# MCU.net
KiCad netlist of a schematic drawn in Altium Designer
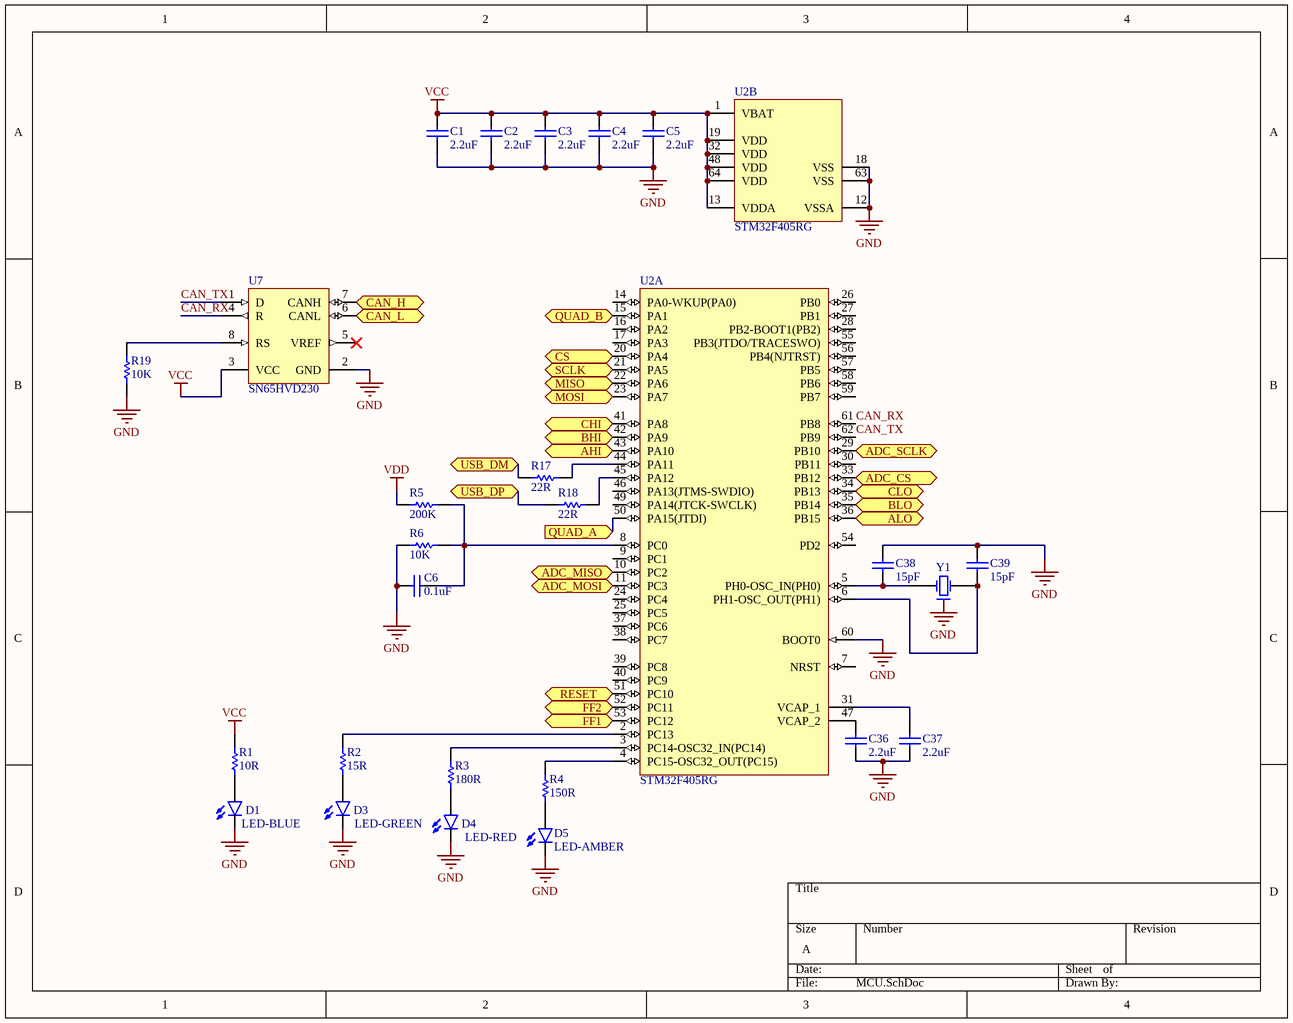
[diagram p0: MCU.SchDoc]

(export (version "E")
  (design (tool "Eeschema 10.0.6"))
  (components
    (comp (ref "C1")
      (value "2.2uF")
      (footprint "CAPC0603(1608)55_N")
      (description "CAP 2.2uF 16V Â±10% 0603 (1608 Metric) Thickness 0.55mm SMD")
      (fields (field (name "TOLERANCE") "Â±10%"))
      (libsource (lib "Altium Content Vault") (part "CMP-1035-02762-1"))
    )
    (comp (ref "C2")
      (value "2.2uF")
      (footprint "CAPC0603(1608)55_N")
      (description "CAP 2.2uF 16V Â±10% 0603 (1608 Metric) Thickness 0.55mm SMD")
      (fields (field (name "TOLERANCE") "Â±10%"))
      (libsource (lib "Altium Content Vault") (part "CMP-1035-02762-1"))
    )
    (comp (ref "C3")
      (value "2.2uF")
      (footprint "CAPC0603(1608)55_N")
      (description "CAP 2.2uF 16V Â±10% 0603 (1608 Metric) Thickness 0.55mm SMD")
      (fields (field (name "TOLERANCE") "Â±10%"))
      (libsource (lib "Altium Content Vault") (part "CMP-1035-02762-1"))
    )
    (comp (ref "C4")
      (value "2.2uF")
      (footprint "CAPC0603(1608)55_N")
      (description "CAP 2.2uF 16V Â±10% 0603 (1608 Metric) Thickness 0.55mm SMD")
      (fields (field (name "TOLERANCE") "Â±10%"))
      (libsource (lib "Altium Content Vault") (part "CMP-1035-02762-1"))
    )
    (comp (ref "C5")
      (value "2.2uF")
      (footprint "CAPC0603(1608)55_N")
      (description "CAP 2.2uF 16V Â±10% 0603 (1608 Metric) Thickness 0.55mm SMD")
      (fields (field (name "TOLERANCE") "Â±10%"))
      (libsource (lib "Altium Content Vault") (part "CMP-1035-02762-1"))
    )
    (comp (ref "C6")
      (value "0.1uF")
      (footprint "CAPC0603(1608)100_L")
      (description "CAP 100nF 50V Â±5% 0603 (1608 Metric) Thickness 1mm SMD")
      (fields (field (name "TOLERANCE") "Â±5%"))
      (libsource (lib "Altium Content Vault") (part "CMP-1035-02591-1"))
    )
    (comp (ref "C36")
      (value "2.2uF")
      (footprint "CAPC0603(1608)55_N")
      (description "CAP 2.2uF 16V Â±10% 0603 (1608 Metric) Thickness 0.55mm SMD")
      (fields (field (name "TOLERANCE") "Â±10%"))
      (libsource (lib "Altium Content Vault") (part "CMP-1035-02762-1"))
    )
    (comp (ref "C37")
      (value "2.2uF")
      (footprint "CAPC0603(1608)55_N")
      (description "CAP 2.2uF 16V Â±10% 0603 (1608 Metric) Thickness 0.55mm SMD")
      (fields (field (name "TOLERANCE") "Â±10%"))
      (libsource (lib "Altium Content Vault") (part "CMP-1035-02762-1"))
    )
    (comp (ref "C38")
      (value "15pF")
      (footprint "CAPC0603(1608)100_L")
      (description "CAP 15pF 100V Â±0.25pF 0603 (1608 Metric) Thickness 1mm SMD")
      (fields (field (name "TOLERANCE") "Â±0.25pF"))
      (libsource (lib "Altium Content Vault") (part "CAP"))
    )
    (comp (ref "C39")
      (value "15pF")
      (footprint "CAPC0603(1608)100_L")
      (description "CAP 15pF 100V Â±0.25pF 0603 (1608 Metric) Thickness 1mm SMD")
      (fields (field (name "TOLERANCE") "Â±0.25pF"))
      (libsource (lib "Altium Content Vault") (part "CAP"))
    )
    (comp (ref "D1")
      (value "LED-BLUE")
      (footprint "LED-1206")
      (libsource (lib "Components") (part "LED-BLUE1206"))
    )
    (comp (ref "D3")
      (value "LED-GREEN")
      (footprint "LED-1206")
      (libsource (lib "Components") (part "LED-GREEN1206"))
    )
    (comp (ref "D4")
      (value "LED-RED")
      (footprint "LED-1206")
      (libsource (lib "Components") (part "LED-RED1206"))
    )
    (comp (ref "D5")
      (value "LED-AMBER")
      (footprint "LED-1206")
      (libsource (lib "Components") (part "LED-AMBER1206"))
    )
    (comp (ref "R1")
      (value "10R")
      (footprint "RESC0603(1608)_N")
      (description "10R 0.1W 5% 0603 (1608 Metric)  SMD")
      (fields (field (name "TOLERANCE") "5 %") (field (name "POWER") "0.1 W"))
      (libsource (lib "Altium Content Vault") (part "CMP-1012-00026-1"))
    )
    (comp (ref "R2")
      (value "15R")
      (footprint "RESC0603(1608)_N")
      (description "15R 0.1W 5% 0603 (1608 Metric)  SMD")
      (fields (field (name "TOLERANCE") "5 %") (field (name "POWER") "0.1 W"))
      (libsource (lib "Altium Content Vault") (part "CMP-1012-00030-1"))
    )
    (comp (ref "R3")
      (value "180R")
      (footprint "RESC0603(1608)_N")
      (description "180R 0.1W 5% 0603 (1608 Metric)  SMD")
      (fields (field (name "POWER") "0.1 W") (field (name "TOLERANCE") "5 %"))
      (libsource (lib "Altium Content Vault") (part "CMP-1012-00056-1"))
    )
    (comp (ref "R4")
      (value "150R")
      (footprint "RESC0603(1608)_N")
      (description "150R 0.1W 5% 0603 (1608 Metric)  SMD")
      (fields (field (name "POWER") "0.1 W") (field (name "TOLERANCE") "5 %"))
      (libsource (lib "Altium Content Vault") (part "CMP-1012-00054-1"))
    )
    (comp (ref "R5")
      (value "200K")
      (footprint "RESC0603(1608)_N")
      (description "200K 0.1W 5% 0603 (1608 Metric)  SMD")
      (fields (field (name "POWER") "0.1 W") (field (name "TOLERANCE") "5 %"))
      (libsource (lib "Altium Content Vault") (part "CMP-1012-00129-1"))
    )
    (comp (ref "R6")
      (value "10K")
      (footprint "RESC0603(1608)_N")
      (description "10K 0.1W 5% 0603 (1608 Metric)  SMD")
      (fields (field (name "TOLERANCE") "5 %") (field (name "POWER") "0.1 W"))
      (libsource (lib "Altium Content Vault") (part "RES"))
    )
    (comp (ref "R17")
      (value "22R")
      (footprint "RESC0603(1608)_M")
      (description "22R 0.1W 5% 0603 (1608 Metric)  SMD")
      (fields (field (name "POWER") "0.1 W") (field (name "TOLERANCE") "5 %"))
      (libsource (lib "Altium Content Vault") (part "RES"))
    )
    (comp (ref "R18")
      (value "22R")
      (footprint "RESC0603(1608)_M")
      (description "22R 0.1W 5% 0603 (1608 Metric)  SMD")
      (fields (field (name "POWER") "0.1 W") (field (name "TOLERANCE") "5 %"))
      (libsource (lib "Altium Content Vault") (part "RES"))
    )
    (comp (ref "R19")
      (value "10K")
      (footprint "RESC0603(1608)_M")
      (description "10K 0.1W 5% 0603 (1608 Metric)  SMD")
      (fields (field (name "TOLERANCE") "5 %") (field (name "POWER") "0.1 W"))
      (libsource (lib "Altium Content Vault") (part "RES"))
    )
    (comp (ref "U2") (value "STM32F405RG") (libsource (lib "Components") (part "MC-ARM-STM32F4X5-SQ64")))
    (comp (ref "U7")
      (value "SN65HVD230")
      (footprint "D8_N")
      (fields (field (name "MANUFACTURER") "Texas Instruments") (field (name "PARTNUMBER") "SN65HVD230DR"))
      (libsource (lib "Altium Content Vault") (part "CMP-0315-00015-1"))
    )
    (comp (ref "Y1")
      (value "~")
      (footprint "ABRA-ABM3B-4_V")
      (libsource (lib "Components") (part "ABRA-ABM3B-4"))
    )
  )
  (nets
    (net (code "1") (name "/ADC_CS") (class "Default")
      (node (ref "U2") (pin "33") (pinfunction "PB12_33") (pintype "bidirectional"))
    )
    (net (code "2") (name "/ADC_MISO") (class "Default")
      (node (ref "U2") (pin "10") (pinfunction "PC2_10") (pintype "bidirectional"))
    )
    (net (code "3") (name "/ADC_MOSI") (class "Default")
      (node (ref "U2") (pin "11") (pinfunction "PC3_11") (pintype "bidirectional"))
    )
    (net (code "4") (name "/ADC_SCLK") (class "Default")
      (node (ref "U2") (pin "29") (pinfunction "PB10_29") (pintype "bidirectional"))
    )
    (net (code "5") (name "/AHI") (class "Default")
      (node (ref "U2") (pin "43") (pinfunction "PA10_43") (pintype "bidirectional"))
    )
    (net (code "6") (name "/ALO") (class "Default")
      (node (ref "U2") (pin "36") (pinfunction "PB15_36") (pintype "bidirectional"))
    )
    (net (code "7") (name "/BHI") (class "Default")
      (node (ref "U2") (pin "42") (pinfunction "PA9_42") (pintype "bidirectional"))
    )
    (net (code "8") (name "/BLO") (class "Default")
      (node (ref "U2") (pin "35") (pinfunction "PB14_35") (pintype "bidirectional"))
    )
    (net (code "9") (name "/CAN_H") (class "Default")
      (node (ref "U7") (pin "7") (pinfunction "CANH_7") (pintype "bidirectional"))
    )
    (net (code "10") (name "/CAN_L") (class "Default")
      (node (ref "U7") (pin "6") (pinfunction "CANL_6") (pintype "bidirectional"))
    )
    (net (code "11") (name "/CAN_RX") (class "Default")
      (node (ref "U2") (pin "61") (pinfunction "PB8_61") (pintype "bidirectional"))
      (node (ref "U7") (pin "4") (pinfunction "R_4") (pintype "output"))
    )
    (net (code "12") (name "/CAN_TX") (class "Default")
      (node (ref "U2") (pin "62") (pinfunction "PB9_62") (pintype "bidirectional"))
      (node (ref "U7") (pin "1") (pinfunction "D_1") (pintype "input"))
    )
    (net (code "13") (name "/CHI") (class "Default")
      (node (ref "U2") (pin "41") (pinfunction "PA8_41") (pintype "bidirectional"))
    )
    (net (code "14") (name "/CLO") (class "Default")
      (node (ref "U2") (pin "34") (pinfunction "PB13_34") (pintype "bidirectional"))
    )
    (net (code "15") (name "/CS") (class "Default")
      (node (ref "U2") (pin "20") (pinfunction "PA4_20") (pintype "bidirectional"))
    )
    (net (code "16") (name "/FF1") (class "Default")
      (node (ref "U2") (pin "53") (pinfunction "PC12_53") (pintype "bidirectional"))
    )
    (net (code "17") (name "/FF2") (class "Default")
      (node (ref "U2") (pin "52") (pinfunction "PC11_52") (pintype "bidirectional"))
    )
    (net (code "18") (name "/MISO") (class "Default")
      (node (ref "U2") (pin "22") (pinfunction "PA6_22") (pintype "bidirectional"))
    )
    (net (code "19") (name "/MOSI") (class "Default")
      (node (ref "U2") (pin "23") (pinfunction "PA7_23") (pintype "bidirectional"))
    )
    (net (code "20") (name "/QUAD_A") (class "Default")
      (node (ref "U2") (pin "50") (pinfunction "PA15(JTDI)_50") (pintype "bidirectional"))
    )
    (net (code "21") (name "/QUAD_B") (class "Default")
      (node (ref "U2") (pin "15") (pinfunction "PA1_15") (pintype "bidirectional"))
    )
    (net (code "22") (name "/RESET") (class "Default")
      (node (ref "U2") (pin "51") (pinfunction "PC10_51") (pintype "bidirectional"))
    )
    (net (code "23") (name "/SCLK") (class "Default")
      (node (ref "U2") (pin "21") (pinfunction "PA5_21") (pintype "bidirectional"))
    )
    (net (code "24") (name "/USB_DM") (class "Default")
      (node (ref "R17") (pin "1") (pinfunction "1_1") (pintype "passive"))
    )
    (net (code "25") (name "/USB_DP") (class "Default")
      (node (ref "R18") (pin "1") (pinfunction "1_1") (pintype "passive"))
    )
    (net (code "26") (name "GND") (class "Default")
      (node (ref "C1") (pin "1") (pinfunction "1_1") (pintype "passive"))
      (node (ref "C2") (pin "1") (pinfunction "1_1") (pintype "passive"))
      (node (ref "C3") (pin "1") (pinfunction "1_1") (pintype "passive"))
      (node (ref "C36") (pin "1") (pinfunction "1_1") (pintype "passive"))
      (node (ref "C37") (pin "1") (pinfunction "1_1") (pintype "passive"))
      (node (ref "C38") (pin "2") (pinfunction "2_2") (pintype "passive"))
      (node (ref "C39") (pin "2") (pinfunction "2_2") (pintype "passive"))
      (node (ref "C4") (pin "1") (pinfunction "1_1") (pintype "passive"))
      (node (ref "C5") (pin "1") (pinfunction "1_1") (pintype "passive"))
      (node (ref "C6") (pin "1") (pinfunction "1_1") (pintype "passive"))
      (node (ref "D1") (pin "C") (pinfunction "C_C") (pintype "passive"))
      (node (ref "D3") (pin "C") (pinfunction "C_C") (pintype "passive"))
      (node (ref "D4") (pin "C") (pinfunction "C_C") (pintype "passive"))
      (node (ref "D5") (pin "C") (pinfunction "C_C") (pintype "passive"))
      (node (ref "R19") (pin "1") (pinfunction "1_1") (pintype "passive"))
      (node (ref "R6") (pin "1") (pinfunction "1_1") (pintype "passive"))
      (node (ref "U2") (pin "12") (pinfunction "VSSA_12") (pintype "power_in"))
      (node (ref "U2") (pin "18") (pinfunction "VSS_18") (pintype "power_in"))
      (node (ref "U2") (pin "60") (pinfunction "BOOT0_60") (pintype "input"))
      (node (ref "U2") (pin "63") (pinfunction "VSS_63") (pintype "power_in"))
      (node (ref "U7") (pin "2") (pinfunction "GND_2") (pintype "power_in"))
      (node (ref "Y1") (pin "2") (pinfunction "2_2") (pintype "passive"))
    )
    (net (code "27") (name "Net-(D1-PadA)") (class "Default")
      (node (ref "D1") (pin "A") (pinfunction "A_A") (pintype "passive"))
      (node (ref "R1") (pin "1") (pinfunction "1_1") (pintype "passive"))
    )
    (net (code "28") (name "Net-(D3-PadA)") (class "Default")
      (node (ref "D3") (pin "A") (pinfunction "A_A") (pintype "passive"))
      (node (ref "R2") (pin "1") (pinfunction "1_1") (pintype "passive"))
    )
    (net (code "29") (name "Net-(D4-PadA)") (class "Default")
      (node (ref "D4") (pin "A") (pinfunction "A_A") (pintype "passive"))
      (node (ref "R3") (pin "1") (pinfunction "1_1") (pintype "passive"))
    )
    (net (code "30") (name "Net-(D5-PadA)") (class "Default")
      (node (ref "D5") (pin "A") (pinfunction "A_A") (pintype "passive"))
      (node (ref "R4") (pin "1") (pinfunction "1_1") (pintype "passive"))
    )
    (net (code "31") (name "Net-(U2A-PA11)") (class "Default")
      (node (ref "R17") (pin "2") (pinfunction "2_2") (pintype "passive"))
      (node (ref "U2") (pin "44") (pinfunction "PA11_44") (pintype "bidirectional"))
    )
    (net (code "32") (name "Net-(U2A-PA12)") (class "Default")
      (node (ref "R18") (pin "2") (pinfunction "2_2") (pintype "passive"))
      (node (ref "U2") (pin "45") (pinfunction "PA12_45") (pintype "bidirectional"))
    )
    (net (code "33") (name "Net-(U2A-PC0)") (class "Default")
      (node (ref "C6") (pin "2") (pinfunction "2_2") (pintype "passive"))
      (node (ref "R5") (pin "2") (pinfunction "2_2") (pintype "passive"))
      (node (ref "R6") (pin "2") (pinfunction "2_2") (pintype "passive"))
      (node (ref "U2") (pin "8") (pinfunction "PC0_8") (pintype "bidirectional"))
    )
    (net (code "34") (name "Net-(U2A-PC13)") (class "Default")
      (node (ref "R2") (pin "2") (pinfunction "2_2") (pintype "passive"))
      (node (ref "U2") (pin "2") (pinfunction "PC13_2") (pintype "bidirectional"))
    )
    (net (code "35") (name "Net-(U2A-PC14-OSC32_IN(PC14))") (class "Default")
      (node (ref "R3") (pin "2") (pinfunction "2_2") (pintype "passive"))
      (node (ref "U2") (pin "3") (pinfunction "PC14-OSC32_IN(PC14)_3") (pintype "bidirectional"))
    )
    (net (code "36") (name "Net-(U2A-PC15-OSC32_OUT(PC15))") (class "Default")
      (node (ref "R4") (pin "2") (pinfunction "2_2") (pintype "passive"))
      (node (ref "U2") (pin "4") (pinfunction "PC15-OSC32_OUT(PC15)_4") (pintype "bidirectional"))
    )
    (net (code "37") (name "Net-(U2A-PH0-OSC_IN(PH0))") (class "Default")
      (node (ref "C38") (pin "1") (pinfunction "1_1") (pintype "passive"))
      (node (ref "U2") (pin "5") (pinfunction "PH0-OSC_IN(PH0)_5") (pintype "bidirectional"))
      (node (ref "Y1") (pin "1") (pinfunction "X1_1") (pintype "passive"))
    )
    (net (code "38") (name "Net-(U2A-PH1-OSC_OUT(PH1))") (class "Default")
      (node (ref "C39") (pin "1") (pinfunction "1_1") (pintype "passive"))
      (node (ref "U2") (pin "6") (pinfunction "PH1-OSC_OUT(PH1)_6") (pintype "bidirectional"))
      (node (ref "Y1") (pin "3") (pinfunction "X2_3") (pintype "passive"))
    )
    (net (code "39") (name "Net-(U2A-VCAP_1)") (class "Default")
      (node (ref "C37") (pin "2") (pinfunction "2_2") (pintype "passive"))
      (node (ref "U2") (pin "31") (pinfunction "VCAP_1_31") (pintype "power_in"))
    )
    (net (code "40") (name "Net-(U2A-VCAP_2)") (class "Default")
      (node (ref "C36") (pin "2") (pinfunction "2_2") (pintype "passive"))
      (node (ref "U2") (pin "47") (pinfunction "VCAP_2_47") (pintype "power_in"))
    )
    (net (code "41") (name "Net-(U7-RS)") (class "Default")
      (node (ref "R19") (pin "2") (pinfunction "2_2") (pintype "passive"))
      (node (ref "U7") (pin "8") (pinfunction "RS_8") (pintype "input"))
    )
    (net (code "42") (name "VCC") (class "Default")
      (node (ref "C1") (pin "2") (pinfunction "2_2") (pintype "passive"))
      (node (ref "C2") (pin "2") (pinfunction "2_2") (pintype "passive"))
      (node (ref "C3") (pin "2") (pinfunction "2_2") (pintype "passive"))
      (node (ref "C4") (pin "2") (pinfunction "2_2") (pintype "passive"))
      (node (ref "C5") (pin "2") (pinfunction "2_2") (pintype "passive"))
      (node (ref "R1") (pin "2") (pinfunction "2_2") (pintype "passive"))
      (node (ref "U2") (pin "1") (pinfunction "VBAT_1") (pintype "power_in"))
      (node (ref "U2") (pin "13") (pinfunction "VDDA_13") (pintype "power_in"))
      (node (ref "U2") (pin "19") (pinfunction "VDD_19") (pintype "power_in"))
      (node (ref "U2") (pin "32") (pinfunction "VDD_32") (pintype "power_in"))
      (node (ref "U2") (pin "48") (pinfunction "VDD_48") (pintype "power_in"))
      (node (ref "U2") (pin "64") (pinfunction "VDD_64") (pintype "power_in"))
      (node (ref "U7") (pin "3") (pinfunction "VCC_3") (pintype "power_in"))
    )
    (net (code "43") (name "VDD") (class "Default")
      (node (ref "R5") (pin "1") (pinfunction "1_1") (pintype "passive"))
    )
    (net (code "44") (name "unconnected-(U2A-NRST-Pad7)") (class "Default")
      (node (ref "U2") (pin "7") (pinfunction "NRST_7") (pintype "bidirectional"))
    )
    (net (code "45") (name "unconnected-(U2A-PA0-WKUP(PA0)-Pad14)") (class "Default")
      (node (ref "U2") (pin "14") (pinfunction "PA0-WKUP(PA0)_14") (pintype "bidirectional"))
    )
    (net (code "46") (name "unconnected-(U2A-PA2-Pad16)") (class "Default")
      (node (ref "U2") (pin "16") (pinfunction "PA2_16") (pintype "bidirectional"))
    )
    (net (code "47") (name "unconnected-(U2A-PA3-Pad17)") (class "Default")
      (node (ref "U2") (pin "17") (pinfunction "PA3_17") (pintype "bidirectional"))
    )
    (net (code "48") (name "unconnected-(U2A-PA13(JTMS-SWDIO)-Pad46)") (class "Default")
      (node (ref "U2") (pin "46") (pinfunction "PA13(JTMS-SWDIO)_46") (pintype "bidirectional"))
    )
    (net (code "49") (name "unconnected-(U2A-PA14(JTCK-SWCLK)-Pad49)") (class "Default")
      (node (ref "U2") (pin "49") (pinfunction "PA14(JTCK-SWCLK)_49") (pintype "bidirectional"))
    )
    (net (code "50") (name "unconnected-(U2A-PB0-Pad26)") (class "Default")
      (node (ref "U2") (pin "26") (pinfunction "PB0_26") (pintype "bidirectional"))
    )
    (net (code "51") (name "unconnected-(U2A-PB1-Pad27)") (class "Default")
      (node (ref "U2") (pin "27") (pinfunction "PB1_27") (pintype "bidirectional"))
    )
    (net (code "52") (name "unconnected-(U2A-PB2-BOOT1(PB2)-Pad28)") (class "Default")
      (node (ref "U2") (pin "28") (pinfunction "PB2-BOOT1(PB2)_28") (pintype "bidirectional"))
    )
    (net (code "53") (name "unconnected-(U2A-PB3(JTDO{slash}TRACESWO)-Pad55)") (class "Default")
      (node (ref "U2") (pin "55") (pinfunction "PB3(JTDO/TRACESWO)_55") (pintype "bidirectional"))
    )
    (net (code "54") (name "unconnected-(U2A-PB4(NJTRST)-Pad56)") (class "Default")
      (node (ref "U2") (pin "56") (pinfunction "PB4(NJTRST)_56") (pintype "bidirectional"))
    )
    (net (code "55") (name "unconnected-(U2A-PB5-Pad57)") (class "Default")
      (node (ref "U2") (pin "57") (pinfunction "PB5_57") (pintype "bidirectional"))
    )
    (net (code "56") (name "unconnected-(U2A-PB6-Pad58)") (class "Default")
      (node (ref "U2") (pin "58") (pinfunction "PB6_58") (pintype "bidirectional"))
    )
    (net (code "57") (name "unconnected-(U2A-PB7-Pad59)") (class "Default")
      (node (ref "U2") (pin "59") (pinfunction "PB7_59") (pintype "bidirectional"))
    )
    (net (code "58") (name "unconnected-(U2A-PB11-Pad30)") (class "Default")
      (node (ref "U2") (pin "30") (pinfunction "PB11_30") (pintype "bidirectional"))
    )
    (net (code "59") (name "unconnected-(U2A-PC1-Pad9)") (class "Default")
      (node (ref "U2") (pin "9") (pinfunction "PC1_9") (pintype "bidirectional"))
    )
    (net (code "60") (name "unconnected-(U2A-PC4-Pad24)") (class "Default")
      (node (ref "U2") (pin "24") (pinfunction "PC4_24") (pintype "bidirectional"))
    )
    (net (code "61") (name "unconnected-(U2A-PC5-Pad25)") (class "Default")
      (node (ref "U2") (pin "25") (pinfunction "PC5_25") (pintype "bidirectional"))
    )
    (net (code "62") (name "unconnected-(U2A-PC6-Pad37)") (class "Default")
      (node (ref "U2") (pin "37") (pinfunction "PC6_37") (pintype "bidirectional"))
    )
    (net (code "63") (name "unconnected-(U2A-PC7-Pad38)") (class "Default")
      (node (ref "U2") (pin "38") (pinfunction "PC7_38") (pintype "bidirectional"))
    )
    (net (code "64") (name "unconnected-(U2A-PC8-Pad39)") (class "Default")
      (node (ref "U2") (pin "39") (pinfunction "PC8_39") (pintype "bidirectional"))
    )
    (net (code "65") (name "unconnected-(U2A-PC9-Pad40)") (class "Default")
      (node (ref "U2") (pin "40") (pinfunction "PC9_40") (pintype "bidirectional"))
    )
    (net (code "66") (name "unconnected-(U2A-PD2-Pad54)") (class "Default")
      (node (ref "U2") (pin "54") (pinfunction "PD2_54") (pintype "bidirectional"))
    )
    (net (code "67") (name "unconnected-(U7-VREF-Pad5)") (class "Default")
      (node (ref "U7") (pin "5") (pinfunction "VREF_5") (pintype "output+no_connect"))
    )
  )
)
